# BC5.net
KiCad netlist of a schematic drawn in EAGLE
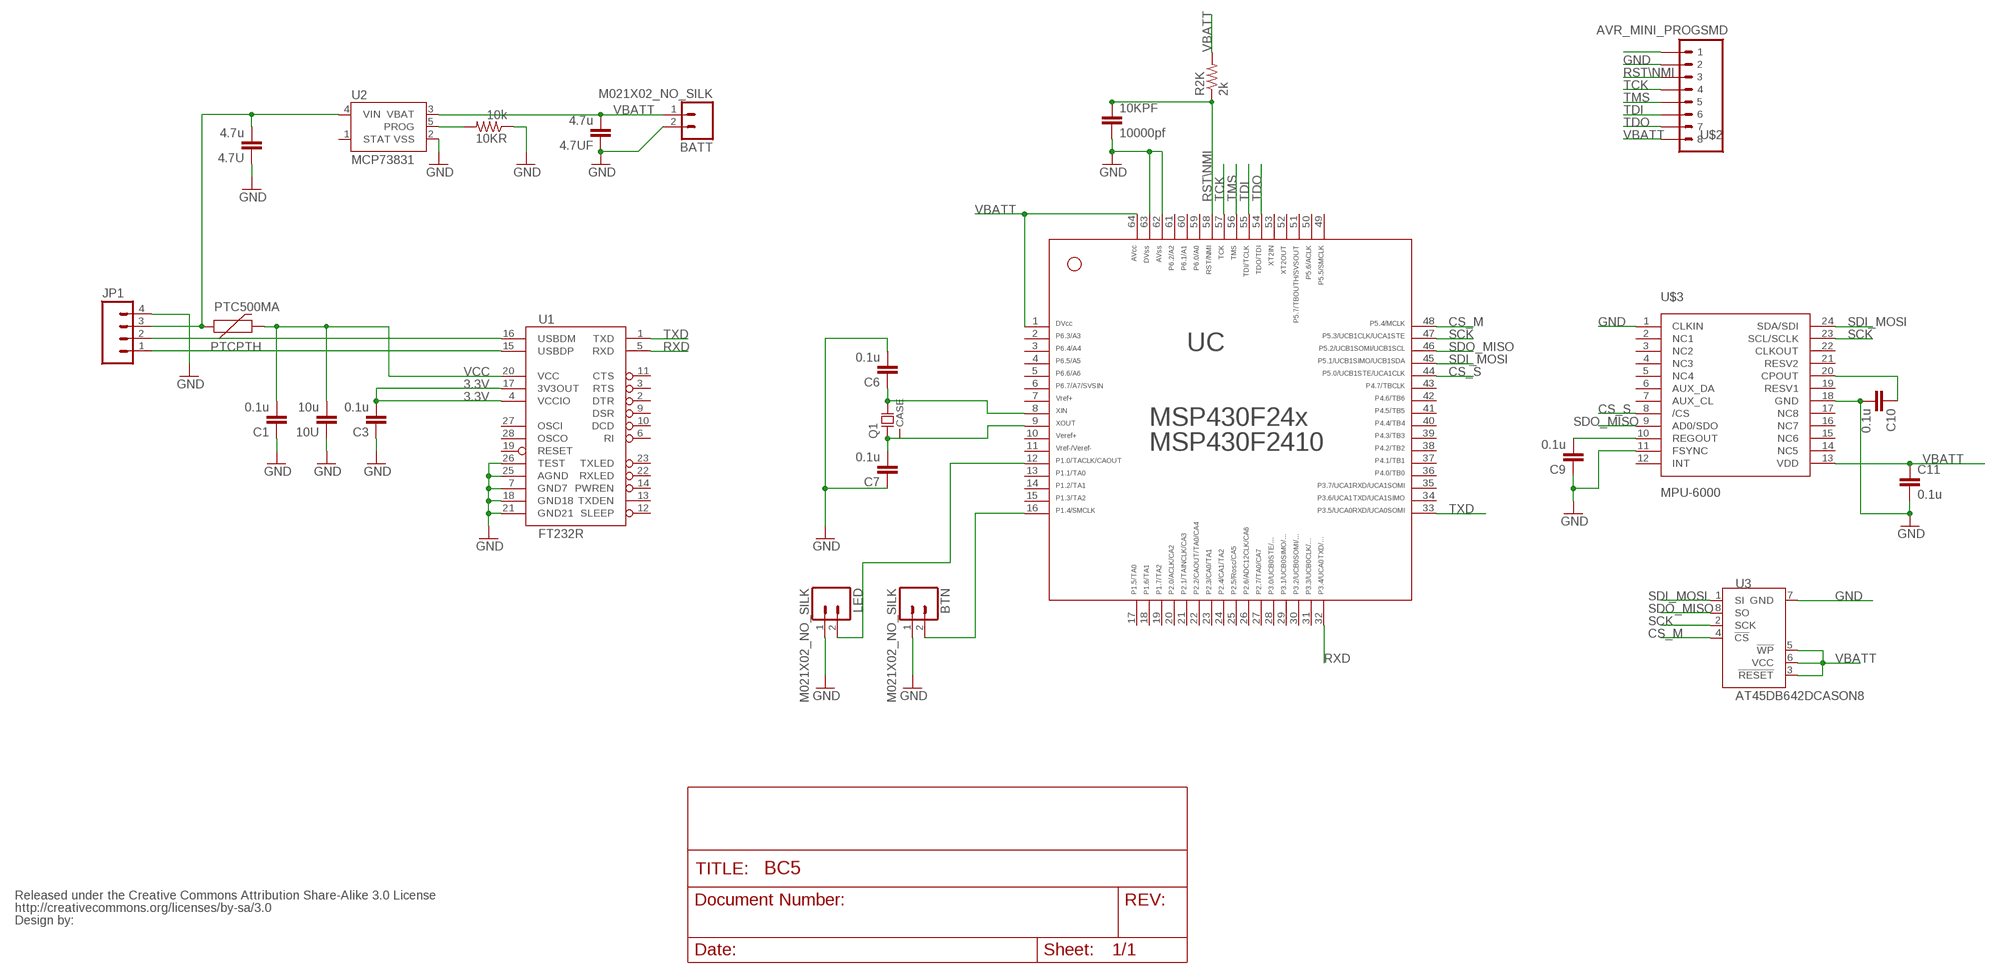
[diagram p0: schematic, sheet 1]

(export (version "E")
  (design (tool "Eeschema 10.0.6"))
  (components
    (comp (ref "4.7U")
      (value "4.7u")
      (footprint "eagle-import:0402-CAP")
      (libsource (lib "eagle-import") (part "CAP0402-CAP"))
    )
    (comp (ref "4.7UF")
      (value "4.7u")
      (footprint "eagle-import:0402-CAP")
      (libsource (lib "eagle-import") (part "CAP0402-CAP"))
    )
    (comp (ref "10KPF")
      (value "10000pf")
      (footprint "eagle-import:CAP-PTH-SMALLEZ")
      (libsource (lib "eagle-import") (part "SparkFun-Passives_CAPEZ"))
    )
    (comp (ref "10KR")
      (value "10k")
      (footprint "eagle-import:0402-RES")
      (libsource (lib "eagle-import") (part "RESISTOR0402-RES"))
    )
    (comp (ref "10U")
      (value "10u")
      (footprint "eagle-import:0402-CAP")
      (libsource (lib "eagle-import") (part "CAP0402-CAP"))
    )
    (comp (ref "BATT")
      (value "M021X02_NO_SILK")
      (footprint "eagle-import:1X02_NO_SILK")
      (libsource (lib "eagle-import") (part "M021X02_NO_SILK"))
    )
    (comp (ref "BTN")
      (value "M021X02_NO_SILK")
      (footprint "eagle-import:1X02_NO_SILK")
      (libsource (lib "eagle-import") (part "M021X02_NO_SILK"))
    )
    (comp (ref "C1")
      (value "0.1u")
      (footprint "eagle-import:0402-CAP")
      (libsource (lib "eagle-import") (part "CAP0402-CAP"))
    )
    (comp (ref "C3")
      (value "0.1u")
      (footprint "eagle-import:0402-CAP")
      (libsource (lib "eagle-import") (part "CAP0402-CAP"))
    )
    (comp (ref "C6")
      (value "0.1u")
      (footprint "eagle-import:0402-CAP")
      (libsource (lib "eagle-import") (part "CAP0402-CAP"))
    )
    (comp (ref "C7")
      (value "0.1u")
      (footprint "eagle-import:0402-CAP")
      (libsource (lib "eagle-import") (part "CAP0402-CAP"))
    )
    (comp (ref "C9")
      (value "0.1u")
      (footprint "eagle-import:0402-CAP")
      (libsource (lib "eagle-import") (part "CAP0402-CAP"))
    )
    (comp (ref "C10")
      (value "0.1u")
      (footprint "eagle-import:0402-CAP")
      (libsource (lib "eagle-import") (part "CAP0402-CAP"))
    )
    (comp (ref "C11")
      (value "0.1u")
      (footprint "eagle-import:0402-CAP")
      (libsource (lib "eagle-import") (part "CAP0402-CAP"))
    )
    (comp (ref "JP1")
      (value "M04LOCK")
      (footprint "eagle-import:1X04_LOCK")
      (libsource (lib "eagle-import") (part "M04LOCK"))
    )
    (comp (ref "LED")
      (value "M021X02_NO_SILK")
      (footprint "eagle-import:1X02_NO_SILK")
      (libsource (lib "eagle-import") (part "M021X02_NO_SILK"))
    )
    (comp (ref "PTC500MA")
      (value "PTCPTH")
      (footprint "eagle-import:PTC")
      (libsource (lib "eagle-import") (part "PTCPTH"))
    )
    (comp (ref "Q1")
      (value "MS1V-T1K-32.768KHZ/12.5PF/20PPM/TA/QC")
      (footprint "eagle-import:MS1V-T1K")
      (libsource (lib "eagle-import") (part "MS1V-T1K-32.768KHZ/12.5PF/20PPM/TA/QC"))
    )
    (comp (ref "R2K")
      (value "2k")
      (footprint "eagle-import:0204_5")
      (libsource (lib "eagle-import") (part "R-US_0204/5"))
    )
    (comp (ref "U$1")
      (value "CREATIVE_COMMONS")
      (footprint "eagle-import:CREATIVE_COMMONS")
      (libsource (lib "eagle-import") (part "CREATIVE_COMMONS"))
    )
    (comp (ref "U$2")
      (value "AVR_MINI_PROGSMD")
      (footprint "eagle-import:AVR_MINI_PROG")
      (libsource (lib "eagle-import") (part "AVR_MINI_PROGSMD"))
    )
    (comp (ref "U$3")
      (value "MPU-6000")
      (footprint "eagle-import:QFN-24")
      (libsource (lib "eagle-import") (part "MPU-6000"))
    )
    (comp (ref "U1")
      (value "FT232R")
      (footprint "eagle-import:SSOP28DB")
      (libsource (lib "eagle-import") (part "FT232RLSSOP"))
    )
    (comp (ref "U2")
      (value "MCP73831")
      (footprint "eagle-import:SOT23-5")
      (libsource (lib "eagle-import") (part "MCP73831"))
    )
    (comp (ref "U3")
      (value "AT45DB642DCASON8")
      (footprint "eagle-import:CASON8")
      (libsource (lib "eagle-import") (part "AT45DB642DCASON8"))
    )
    (comp (ref "UC")
      (value "F24[X/10]---PM64")
      (footprint "eagle-import:PM_PAG64")
      (libsource (lib "eagle-import") (part "F24[X/10]---PM64"))
    )
  )
  (nets
    (net (code "1") (name "/3.3V") (class "Default")
      (node (ref "C3") (pin "2") (pinfunction "2_2") (pintype "passive"))
      (node (ref "U1") (pin "17") (pinfunction "3V3OUT_17") (pintype "output"))
      (node (ref "U1") (pin "4") (pinfunction "VCCIO_4") (pintype "power_in"))
    )
    (net (code "2") (name "/CS_M") (class "Default")
      (node (ref "U3") (pin "4") (pinfunction "~{CS}_4") (pintype "input"))
      (node (ref "UC") (pin "48") (pinfunction "48_48") (pintype "bidirectional"))
    )
    (net (code "3") (name "/CS_S") (class "Default")
      (node (ref "U$3") (pin "8") (pinfunction "/CS_8") (pintype "bidirectional"))
      (node (ref "UC") (pin "44") (pinfunction "44_44") (pintype "bidirectional"))
    )
    (net (code "4") (name "/RST\\NMI") (class "Default")
      (node (ref "10KPF") (pin "1") (pinfunction "1_1") (pintype "passive"))
      (node (ref "R2K") (pin "1") (pinfunction "1_1") (pintype "passive"))
      (node (ref "U$2") (pin "3") (pinfunction "3_3") (pintype "passive"))
      (node (ref "UC") (pin "58") (pinfunction "58_58") (pintype "input"))
    )
    (net (code "5") (name "/RXD") (class "Default")
      (node (ref "U1") (pin "5") (pinfunction "RXD_5") (pintype "input"))
      (node (ref "UC") (pin "32") (pinfunction "32_32") (pintype "bidirectional"))
    )
    (net (code "6") (name "/SCK") (class "Default")
      (node (ref "U$3") (pin "23") (pinfunction "SCL/SCLK_23") (pintype "bidirectional"))
      (node (ref "U3") (pin "2") (pinfunction "SCK_2") (pintype "input"))
      (node (ref "UC") (pin "47") (pinfunction "47_47") (pintype "bidirectional"))
    )
    (net (code "7") (name "/SDI_MOSI") (class "Default")
      (node (ref "U$3") (pin "24") (pinfunction "SDA/SDI_24") (pintype "bidirectional"))
      (node (ref "U3") (pin "1") (pinfunction "SI_1") (pintype "input"))
      (node (ref "UC") (pin "45") (pinfunction "45_45") (pintype "bidirectional"))
    )
    (net (code "8") (name "/SDO_MISO") (class "Default")
      (node (ref "U$3") (pin "9") (pinfunction "AD0/SDO_9") (pintype "bidirectional"))
      (node (ref "U3") (pin "8") (pinfunction "SO_8") (pintype "output"))
      (node (ref "UC") (pin "46") (pinfunction "46_46") (pintype "bidirectional"))
    )
    (net (code "9") (name "/TCK") (class "Default")
      (node (ref "U$2") (pin "4") (pinfunction "4_4") (pintype "passive"))
      (node (ref "UC") (pin "57") (pinfunction "57_57") (pintype "input"))
    )
    (net (code "10") (name "/TDI") (class "Default")
      (node (ref "U$2") (pin "6") (pinfunction "6_6") (pintype "passive"))
      (node (ref "UC") (pin "55") (pinfunction "55_55") (pintype "input"))
    )
    (net (code "11") (name "/TDO") (class "Default")
      (node (ref "U$2") (pin "7") (pinfunction "7_7") (pintype "passive"))
      (node (ref "UC") (pin "54") (pinfunction "54_54") (pintype "bidirectional"))
    )
    (net (code "12") (name "/TMS") (class "Default")
      (node (ref "U$2") (pin "5") (pinfunction "5_5") (pintype "passive"))
      (node (ref "UC") (pin "56") (pinfunction "56_56") (pintype "input"))
    )
    (net (code "13") (name "/TXD") (class "Default")
      (node (ref "U1") (pin "1") (pinfunction "TXD_1") (pintype "output"))
      (node (ref "UC") (pin "33") (pinfunction "33_33") (pintype "bidirectional"))
    )
    (net (code "14") (name "/VBATT") (class "Default")
      (node (ref "4.7UF") (pin "2") (pinfunction "2_2") (pintype "passive"))
      (node (ref "BATT") (pin "1") (pinfunction "1_1") (pintype "passive"))
      (node (ref "C11") (pin "1") (pinfunction "1_1") (pintype "passive"))
      (node (ref "R2K") (pin "2") (pinfunction "2_2") (pintype "passive"))
      (node (ref "U$2") (pin "8") (pinfunction "8_8") (pintype "passive"))
      (node (ref "U$3") (pin "13") (pinfunction "VDD_13") (pintype "bidirectional"))
      (node (ref "U2") (pin "3") (pinfunction "VBAT_3") (pintype "power_in"))
      (node (ref "U3") (pin "3") (pinfunction "~{RESET}_3") (pintype "input"))
      (node (ref "U3") (pin "5") (pinfunction "~{WP}_5") (pintype "input"))
      (node (ref "U3") (pin "6") (pinfunction "VCC_6") (pintype "power_in"))
      (node (ref "UC") (pin "1") (pinfunction "1_1") (pintype "power_in"))
      (node (ref "UC") (pin "64") (pinfunction "64_64") (pintype "power_in"))
    )
    (net (code "15") (name "/VCC") (class "Default")
      (node (ref "10U") (pin "2") (pinfunction "2_2") (pintype "passive"))
      (node (ref "C1") (pin "2") (pinfunction "2_2") (pintype "passive"))
      (node (ref "PTC500MA") (pin "P$2") (pinfunction "2_P$2") (pintype "bidirectional"))
      (node (ref "U1") (pin "20") (pinfunction "VCC_20") (pintype "power_in"))
    )
    (net (code "16") (name "GND") (class "Default")
      (node (ref "10KPF") (pin "2") (pinfunction "2_2") (pintype "passive"))
      (node (ref "10KR") (pin "1") (pinfunction "1_1") (pintype "passive"))
      (node (ref "10U") (pin "1") (pinfunction "1_1") (pintype "passive"))
      (node (ref "4.7U") (pin "1") (pinfunction "1_1") (pintype "passive"))
      (node (ref "4.7UF") (pin "1") (pinfunction "1_1") (pintype "passive"))
      (node (ref "BATT") (pin "2") (pinfunction "2_2") (pintype "passive"))
      (node (ref "BTN") (pin "1") (pinfunction "1_1") (pintype "passive"))
      (node (ref "C1") (pin "1") (pinfunction "1_1") (pintype "passive"))
      (node (ref "C10") (pin "2") (pinfunction "2_2") (pintype "passive"))
      (node (ref "C11") (pin "2") (pinfunction "2_2") (pintype "passive"))
      (node (ref "C3") (pin "1") (pinfunction "1_1") (pintype "passive"))
      (node (ref "C6") (pin "2") (pinfunction "2_2") (pintype "passive"))
      (node (ref "C7") (pin "1") (pinfunction "1_1") (pintype "passive"))
      (node (ref "C9") (pin "1") (pinfunction "1_1") (pintype "passive"))
      (node (ref "JP1") (pin "4") (pinfunction "4_4") (pintype "passive"))
      (node (ref "LED") (pin "1") (pinfunction "1_1") (pintype "passive"))
      (node (ref "U$2") (pin "2") (pinfunction "2_2") (pintype "passive"))
      (node (ref "U$3") (pin "1") (pinfunction "CLKIN_1") (pintype "bidirectional"))
      (node (ref "U$3") (pin "11") (pinfunction "FSYNC_11") (pintype "bidirectional"))
      (node (ref "U$3") (pin "18") (pinfunction "GND_18") (pintype "bidirectional"))
      (node (ref "U1") (pin "18") (pinfunction "GND18_18") (pintype "power_in"))
      (node (ref "U1") (pin "21") (pinfunction "GND21_21") (pintype "power_in"))
      (node (ref "U1") (pin "25") (pinfunction "AGND_25") (pintype "power_in"))
      (node (ref "U1") (pin "26") (pinfunction "TEST_26") (pintype "input"))
      (node (ref "U1") (pin "7") (pinfunction "GND7_7") (pintype "power_in"))
      (node (ref "U2") (pin "2") (pinfunction "VSS_2") (pintype "power_in"))
      (node (ref "U3") (pin "7") (pinfunction "GND_7") (pintype "power_in"))
      (node (ref "UC") (pin "62") (pinfunction "62_62") (pintype "power_in"))
      (node (ref "UC") (pin "63") (pinfunction "63_63") (pintype "power_in"))
    )
    (net (code "17") (name "Net-(BTN-Pad2)") (class "Default")
      (node (ref "BTN") (pin "2") (pinfunction "2_2") (pintype "passive"))
      (node (ref "UC") (pin "16") (pinfunction "16_16") (pintype "bidirectional"))
    )
    (net (code "18") (name "Net-(C6-Pad1)") (class "Default")
      (node (ref "C6") (pin "1") (pinfunction "1_1") (pintype "passive"))
      (node (ref "Q1") (pin "2") (pinfunction "2_2") (pintype "passive"))
      (node (ref "UC") (pin "8") (pinfunction "8_8") (pintype "input"))
    )
    (net (code "19") (name "Net-(C7-Pad2)") (class "Default")
      (node (ref "C7") (pin "2") (pinfunction "2_2") (pintype "passive"))
      (node (ref "Q1") (pin "1") (pinfunction "1_1") (pintype "passive"))
      (node (ref "UC") (pin "9") (pinfunction "9_9") (pintype "output"))
    )
    (net (code "20") (name "Net-(LED-Pad2)") (class "Default")
      (node (ref "LED") (pin "2") (pinfunction "2_2") (pintype "passive"))
      (node (ref "UC") (pin "12") (pinfunction "12_12") (pintype "bidirectional"))
    )
    (net (code "21") (name "Net-(PTC500MA-1)") (class "Default")
      (node (ref "4.7U") (pin "2") (pinfunction "2_2") (pintype "passive"))
      (node (ref "JP1") (pin "3") (pinfunction "3_3") (pintype "passive"))
      (node (ref "PTC500MA") (pin "P$1") (pinfunction "1_P$1") (pintype "bidirectional"))
      (node (ref "U2") (pin "4") (pinfunction "VIN_4") (pintype "power_in"))
    )
    (net (code "22") (name "Net-(U$3-CPOUT)") (class "Default")
      (node (ref "C10") (pin "1") (pinfunction "1_1") (pintype "passive"))
      (node (ref "U$3") (pin "20") (pinfunction "CPOUT_20") (pintype "bidirectional"))
    )
    (net (code "23") (name "Net-(U$3-REGOUT)") (class "Default")
      (node (ref "C9") (pin "2") (pinfunction "2_2") (pintype "passive"))
      (node (ref "U$3") (pin "10") (pinfunction "REGOUT_10") (pintype "bidirectional"))
    )
    (net (code "24") (name "Net-(U1-USBDM)") (class "Default")
      (node (ref "JP1") (pin "2") (pinfunction "2_2") (pintype "passive"))
      (node (ref "U1") (pin "16") (pinfunction "USBDM_16") (pintype "bidirectional"))
    )
    (net (code "25") (name "Net-(U1-USBDP)") (class "Default")
      (node (ref "JP1") (pin "1") (pinfunction "1_1") (pintype "passive"))
      (node (ref "U1") (pin "15") (pinfunction "USBDP_15") (pintype "bidirectional"))
    )
    (net (code "26") (name "Net-(U2-PROG)") (class "Default")
      (node (ref "10KR") (pin "2") (pinfunction "2_2") (pintype "passive"))
      (node (ref "U2") (pin "5") (pinfunction "PROG_5") (pintype "input"))
    )
    (net (code "27") (name "unconnected-(Q1-PadCASE)") (class "Default")
      (node (ref "Q1") (pin "CASE") (pinfunction "CASE_CASE") (pintype "passive"))
    )
    (net (code "28") (name "unconnected-(U$2-Pad1)") (class "Default")
      (node (ref "U$2") (pin "1") (pinfunction "1_1") (pintype "passive"))
    )
    (net (code "29") (name "unconnected-(U$3-AUX_CL-Pad7)") (class "Default")
      (node (ref "U$3") (pin "7") (pinfunction "AUX_CL_7") (pintype "bidirectional"))
    )
    (net (code "30") (name "unconnected-(U$3-AUX_DA-Pad6)") (class "Default")
      (node (ref "U$3") (pin "6") (pinfunction "AUX_DA_6") (pintype "bidirectional"))
    )
    (net (code "31") (name "unconnected-(U$3-CLKOUT-Pad22)") (class "Default")
      (node (ref "U$3") (pin "22") (pinfunction "CLKOUT_22") (pintype "bidirectional"))
    )
    (net (code "32") (name "unconnected-(U$3-INT-Pad12)") (class "Default")
      (node (ref "U$3") (pin "12") (pinfunction "INT_12") (pintype "bidirectional"))
    )
    (net (code "33") (name "unconnected-(U$3-NC1-Pad2)") (class "Default")
      (node (ref "U$3") (pin "2") (pinfunction "NC1_2") (pintype "bidirectional"))
    )
    (net (code "34") (name "unconnected-(U$3-NC2-Pad3)") (class "Default")
      (node (ref "U$3") (pin "3") (pinfunction "NC2_3") (pintype "bidirectional"))
    )
    (net (code "35") (name "unconnected-(U$3-NC3-Pad4)") (class "Default")
      (node (ref "U$3") (pin "4") (pinfunction "NC3_4") (pintype "bidirectional"))
    )
    (net (code "36") (name "unconnected-(U$3-NC4-Pad5)") (class "Default")
      (node (ref "U$3") (pin "5") (pinfunction "NC4_5") (pintype "bidirectional"))
    )
    (net (code "37") (name "unconnected-(U$3-NC5-Pad14)") (class "Default")
      (node (ref "U$3") (pin "14") (pinfunction "NC5_14") (pintype "bidirectional"))
    )
    (net (code "38") (name "unconnected-(U$3-NC6-Pad15)") (class "Default")
      (node (ref "U$3") (pin "15") (pinfunction "NC6_15") (pintype "bidirectional"))
    )
    (net (code "39") (name "unconnected-(U$3-NC7-Pad16)") (class "Default")
      (node (ref "U$3") (pin "16") (pinfunction "NC7_16") (pintype "bidirectional"))
    )
    (net (code "40") (name "unconnected-(U$3-NC8-Pad17)") (class "Default")
      (node (ref "U$3") (pin "17") (pinfunction "NC8_17") (pintype "bidirectional"))
    )
    (net (code "41") (name "unconnected-(U$3-RESV1-Pad19)") (class "Default")
      (node (ref "U$3") (pin "19") (pinfunction "RESV1_19") (pintype "bidirectional"))
    )
    (net (code "42") (name "unconnected-(U$3-RESV2-Pad21)") (class "Default")
      (node (ref "U$3") (pin "21") (pinfunction "RESV2_21") (pintype "bidirectional"))
    )
    (net (code "43") (name "unconnected-(U1-CTS-Pad11)") (class "Default")
      (node (ref "U1") (pin "11") (pinfunction "CTS_11") (pintype "input"))
    )
    (net (code "44") (name "unconnected-(U1-DCD-Pad10)") (class "Default")
      (node (ref "U1") (pin "10") (pinfunction "DCD_10") (pintype "input"))
    )
    (net (code "45") (name "unconnected-(U1-DSR-Pad9)") (class "Default")
      (node (ref "U1") (pin "9") (pinfunction "DSR_9") (pintype "input"))
    )
    (net (code "46") (name "unconnected-(U1-DTR-Pad2)") (class "Default")
      (node (ref "U1") (pin "2") (pinfunction "DTR_2") (pintype "output"))
    )
    (net (code "47") (name "unconnected-(U1-OSCI-Pad27)") (class "Default")
      (node (ref "U1") (pin "27") (pinfunction "OSCI_27") (pintype "input"))
    )
    (net (code "48") (name "unconnected-(U1-OSCO-Pad28)") (class "Default")
      (node (ref "U1") (pin "28") (pinfunction "OSCO_28") (pintype "output"))
    )
    (net (code "49") (name "unconnected-(U1-PWREN-Pad14)") (class "Default")
      (node (ref "U1") (pin "14") (pinfunction "PWREN_14") (pintype "input"))
    )
    (net (code "50") (name "unconnected-(U1-RESET-Pad19)") (class "Default")
      (node (ref "U1") (pin "19") (pinfunction "RESET_19") (pintype "input"))
    )
    (net (code "51") (name "unconnected-(U1-RI-Pad6)") (class "Default")
      (node (ref "U1") (pin "6") (pinfunction "RI_6") (pintype "input"))
    )
    (net (code "52") (name "unconnected-(U1-RTS-Pad3)") (class "Default")
      (node (ref "U1") (pin "3") (pinfunction "RTS_3") (pintype "output"))
    )
    (net (code "53") (name "unconnected-(U1-RXLED-Pad22)") (class "Default")
      (node (ref "U1") (pin "22") (pinfunction "RXLED_22") (pintype "input"))
    )
    (net (code "54") (name "unconnected-(U1-SLEEP-Pad12)") (class "Default")
      (node (ref "U1") (pin "12") (pinfunction "SLEEP_12") (pintype "input"))
    )
    (net (code "55") (name "unconnected-(U1-TXDEN-Pad13)") (class "Default")
      (node (ref "U1") (pin "13") (pinfunction "TXDEN_13") (pintype "input"))
    )
    (net (code "56") (name "unconnected-(U1-TXLED-Pad23)") (class "Default")
      (node (ref "U1") (pin "23") (pinfunction "TXLED_23") (pintype "input"))
    )
    (net (code "57") (name "unconnected-(U2-STAT-Pad1)") (class "Default")
      (node (ref "U2") (pin "1") (pinfunction "STAT_1") (pintype "output"))
    )
    (net (code "58") (name "unconnected-(UC-Pad2)") (class "Default")
      (node (ref "UC") (pin "2") (pinfunction "2_2") (pintype "bidirectional"))
    )
    (net (code "59") (name "unconnected-(UC-Pad3)") (class "Default")
      (node (ref "UC") (pin "3") (pinfunction "3_3") (pintype "bidirectional"))
    )
    (net (code "60") (name "unconnected-(UC-Pad4)") (class "Default")
      (node (ref "UC") (pin "4") (pinfunction "4_4") (pintype "bidirectional"))
    )
    (net (code "61") (name "unconnected-(UC-Pad5)") (class "Default")
      (node (ref "UC") (pin "5") (pinfunction "5_5") (pintype "bidirectional"))
    )
    (net (code "62") (name "unconnected-(UC-Pad6)") (class "Default")
      (node (ref "UC") (pin "6") (pinfunction "6_6") (pintype "bidirectional"))
    )
    (net (code "63") (name "unconnected-(UC-Pad7)") (class "Default")
      (node (ref "UC") (pin "7") (pinfunction "7_7") (pintype "output"))
    )
    (net (code "64") (name "unconnected-(UC-Pad10)") (class "Default")
      (node (ref "UC") (pin "10") (pinfunction "10_10") (pintype "output"))
    )
    (net (code "65") (name "unconnected-(UC-Pad11)") (class "Default")
      (node (ref "UC") (pin "11") (pinfunction "11_11") (pintype "input"))
    )
    (net (code "66") (name "unconnected-(UC-Pad13)") (class "Default")
      (node (ref "UC") (pin "13") (pinfunction "13_13") (pintype "bidirectional"))
    )
    (net (code "67") (name "unconnected-(UC-Pad14)") (class "Default")
      (node (ref "UC") (pin "14") (pinfunction "14_14") (pintype "bidirectional"))
    )
    (net (code "68") (name "unconnected-(UC-Pad15)") (class "Default")
      (node (ref "UC") (pin "15") (pinfunction "15_15") (pintype "bidirectional"))
    )
    (net (code "69") (name "unconnected-(UC-Pad17)") (class "Default")
      (node (ref "UC") (pin "17") (pinfunction "17_17") (pintype "bidirectional"))
    )
    (net (code "70") (name "unconnected-(UC-Pad18)") (class "Default")
      (node (ref "UC") (pin "18") (pinfunction "18_18") (pintype "bidirectional"))
    )
    (net (code "71") (name "unconnected-(UC-Pad19)") (class "Default")
      (node (ref "UC") (pin "19") (pinfunction "19_19") (pintype "bidirectional"))
    )
    (net (code "72") (name "unconnected-(UC-Pad20)") (class "Default")
      (node (ref "UC") (pin "20") (pinfunction "20_20") (pintype "bidirectional"))
    )
    (net (code "73") (name "unconnected-(UC-Pad21)") (class "Default")
      (node (ref "UC") (pin "21") (pinfunction "21_21") (pintype "bidirectional"))
    )
    (net (code "74") (name "unconnected-(UC-Pad22)") (class "Default")
      (node (ref "UC") (pin "22") (pinfunction "22_22") (pintype "bidirectional"))
    )
    (net (code "75") (name "unconnected-(UC-Pad23)") (class "Default")
      (node (ref "UC") (pin "23") (pinfunction "23_23") (pintype "bidirectional"))
    )
    (net (code "76") (name "unconnected-(UC-Pad24)") (class "Default")
      (node (ref "UC") (pin "24") (pinfunction "24_24") (pintype "bidirectional"))
    )
    (net (code "77") (name "unconnected-(UC-Pad25)") (class "Default")
      (node (ref "UC") (pin "25") (pinfunction "25_25") (pintype "bidirectional"))
    )
    (net (code "78") (name "unconnected-(UC-Pad26)") (class "Default")
      (node (ref "UC") (pin "26") (pinfunction "26_26") (pintype "bidirectional"))
    )
    (net (code "79") (name "unconnected-(UC-Pad27)") (class "Default")
      (node (ref "UC") (pin "27") (pinfunction "27_27") (pintype "bidirectional"))
    )
    (net (code "80") (name "unconnected-(UC-Pad28)") (class "Default")
      (node (ref "UC") (pin "28") (pinfunction "28_28") (pintype "bidirectional"))
    )
    (net (code "81") (name "unconnected-(UC-Pad29)") (class "Default")
      (node (ref "UC") (pin "29") (pinfunction "29_29") (pintype "bidirectional"))
    )
    (net (code "82") (name "unconnected-(UC-Pad30)") (class "Default")
      (node (ref "UC") (pin "30") (pinfunction "30_30") (pintype "bidirectional"))
    )
    (net (code "83") (name "unconnected-(UC-Pad31)") (class "Default")
      (node (ref "UC") (pin "31") (pinfunction "31_31") (pintype "bidirectional"))
    )
    (net (code "84") (name "unconnected-(UC-Pad34)") (class "Default")
      (node (ref "UC") (pin "34") (pinfunction "34_34") (pintype "bidirectional"))
    )
    (net (code "85") (name "unconnected-(UC-Pad35)") (class "Default")
      (node (ref "UC") (pin "35") (pinfunction "35_35") (pintype "bidirectional"))
    )
    (net (code "86") (name "unconnected-(UC-Pad36)") (class "Default")
      (node (ref "UC") (pin "36") (pinfunction "36_36") (pintype "bidirectional"))
    )
    (net (code "87") (name "unconnected-(UC-Pad37)") (class "Default")
      (node (ref "UC") (pin "37") (pinfunction "37_37") (pintype "bidirectional"))
    )
    (net (code "88") (name "unconnected-(UC-Pad38)") (class "Default")
      (node (ref "UC") (pin "38") (pinfunction "38_38") (pintype "bidirectional"))
    )
    (net (code "89") (name "unconnected-(UC-Pad39)") (class "Default")
      (node (ref "UC") (pin "39") (pinfunction "39_39") (pintype "bidirectional"))
    )
    (net (code "90") (name "unconnected-(UC-Pad40)") (class "Default")
      (node (ref "UC") (pin "40") (pinfunction "40_40") (pintype "bidirectional"))
    )
    (net (code "91") (name "unconnected-(UC-Pad41)") (class "Default")
      (node (ref "UC") (pin "41") (pinfunction "41_41") (pintype "bidirectional"))
    )
    (net (code "92") (name "unconnected-(UC-Pad42)") (class "Default")
      (node (ref "UC") (pin "42") (pinfunction "42_42") (pintype "bidirectional"))
    )
    (net (code "93") (name "unconnected-(UC-Pad43)") (class "Default")
      (node (ref "UC") (pin "43") (pinfunction "43_43") (pintype "bidirectional"))
    )
    (net (code "94") (name "unconnected-(UC-Pad49)") (class "Default")
      (node (ref "UC") (pin "49") (pinfunction "49_49") (pintype "bidirectional"))
    )
    (net (code "95") (name "unconnected-(UC-Pad50)") (class "Default")
      (node (ref "UC") (pin "50") (pinfunction "50_50") (pintype "bidirectional"))
    )
    (net (code "96") (name "unconnected-(UC-Pad51)") (class "Default")
      (node (ref "UC") (pin "51") (pinfunction "51_51") (pintype "bidirectional"))
    )
    (net (code "97") (name "unconnected-(UC-Pad52)") (class "Default")
      (node (ref "UC") (pin "52") (pinfunction "52_52") (pintype "output"))
    )
    (net (code "98") (name "unconnected-(UC-Pad53)") (class "Default")
      (node (ref "UC") (pin "53") (pinfunction "53_53") (pintype "input"))
    )
    (net (code "99") (name "unconnected-(UC-Pad59)") (class "Default")
      (node (ref "UC") (pin "59") (pinfunction "59_59") (pintype "bidirectional"))
    )
    (net (code "100") (name "unconnected-(UC-Pad60)") (class "Default")
      (node (ref "UC") (pin "60") (pinfunction "60_60") (pintype "bidirectional"))
    )
    (net (code "101") (name "unconnected-(UC-Pad61)") (class "Default")
      (node (ref "UC") (pin "61") (pinfunction "61_61") (pintype "bidirectional"))
    )
  )
)
